# Proton_Schematic_Eagle.net
KiCad netlist of a schematic drawn in EAGLE
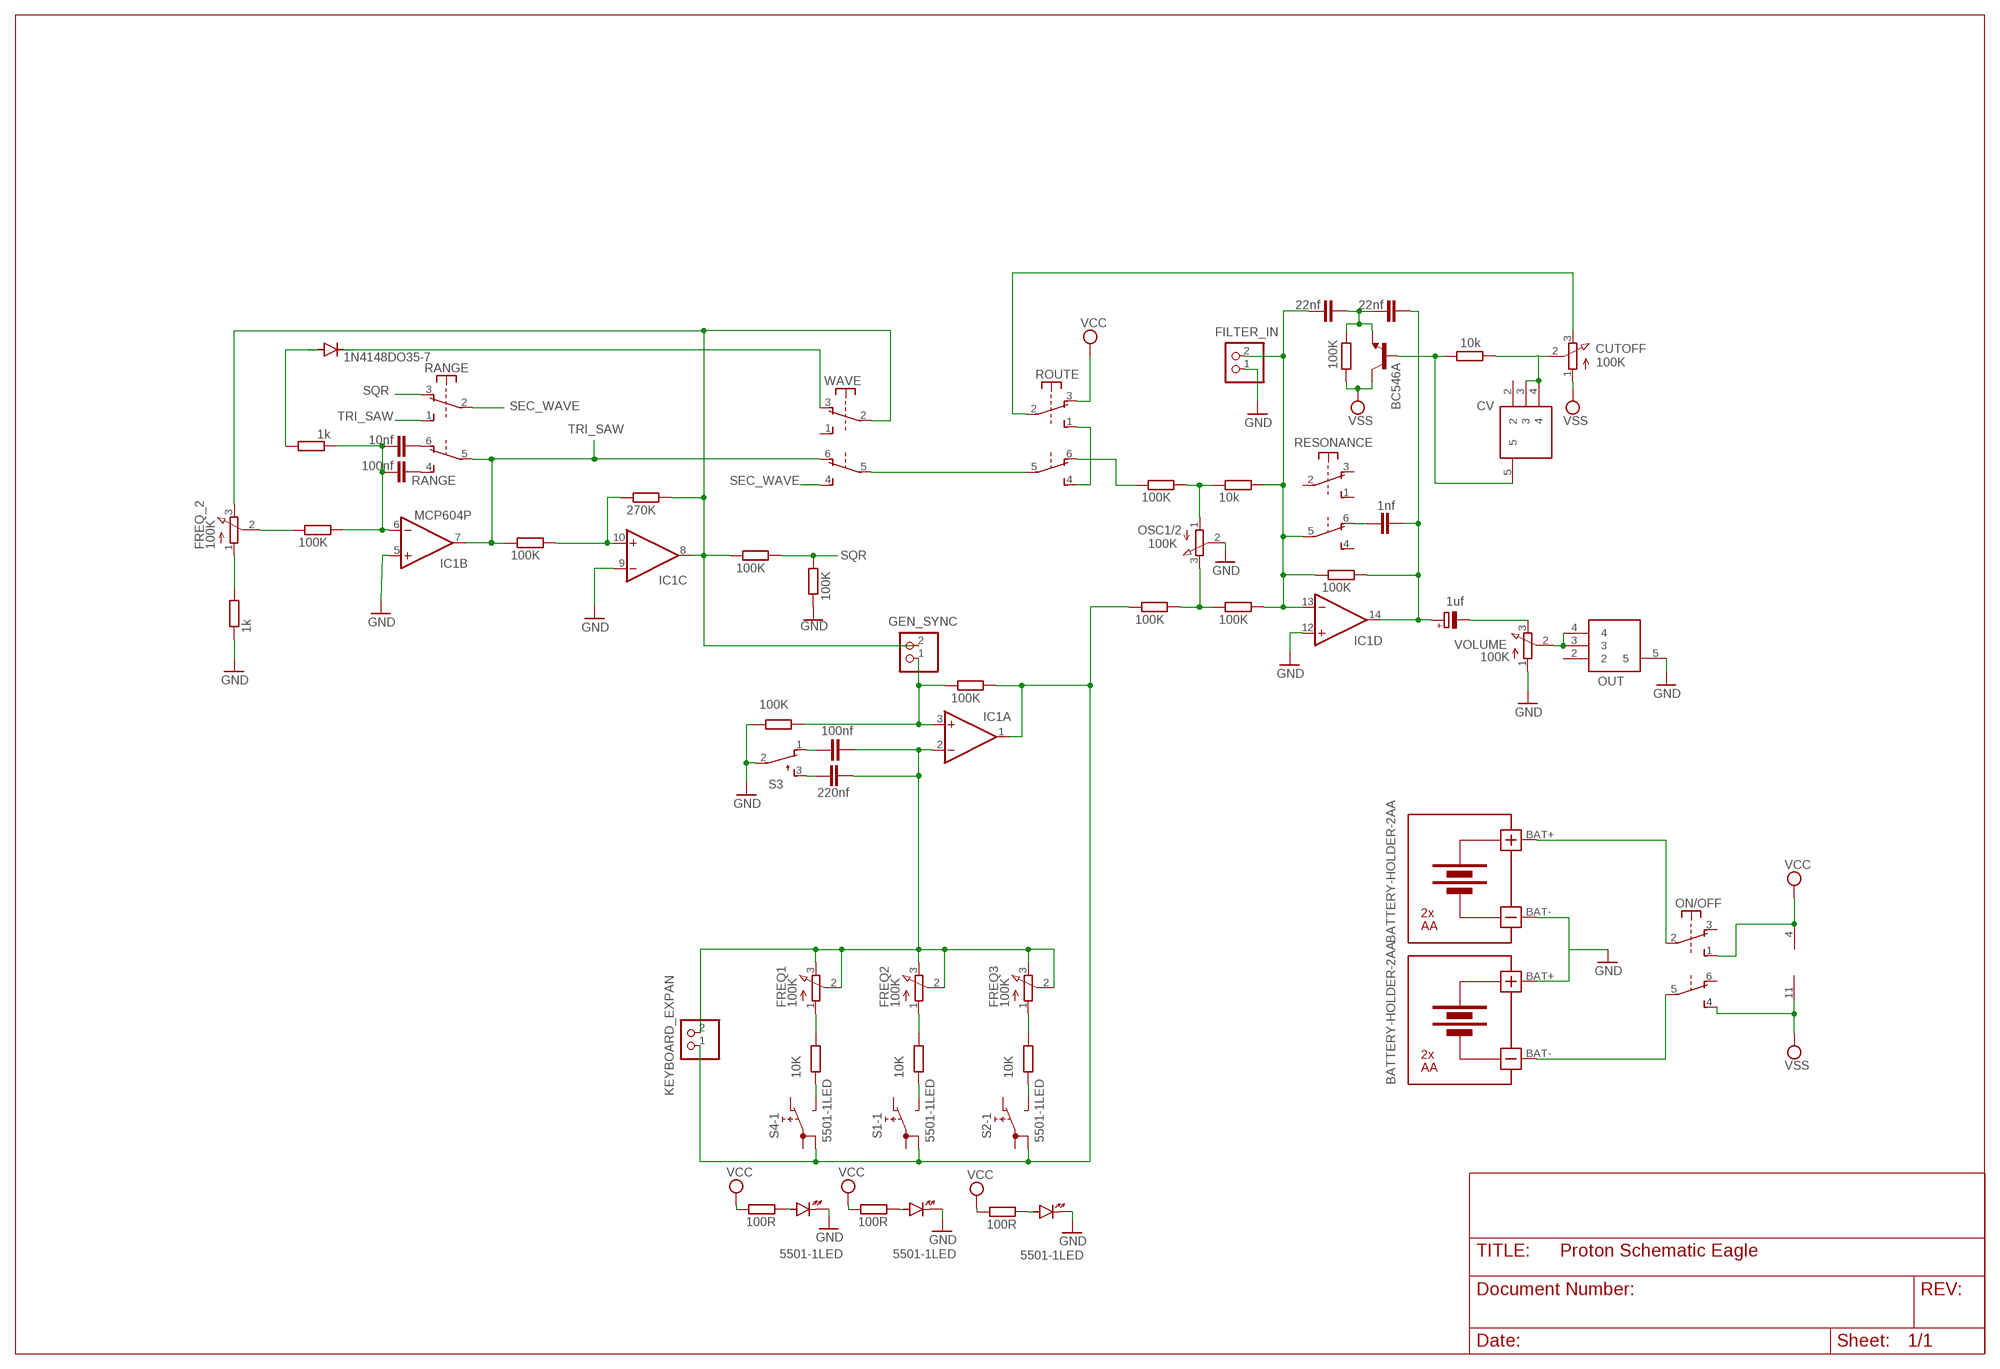
[diagram p0: schematic, sheet 1]

(export (version "E")
  (design (tool "Eeschema 10.0.6"))
  (components
    (comp (ref "1K")
      (value "1k")
      (footprint "eagle-import:0207_10")
      (libsource (lib "eagle-import") (part "R-EU_0207/10"))
    )
    (comp (ref "1K1")
      (value "1k")
      (footprint "eagle-import:0207_10")
      (libsource (lib "eagle-import") (part "R-EU_0207/10"))
    )
    (comp (ref "100K")
      (value "100K")
      (footprint "eagle-import:0207_10")
      (libsource (lib "eagle-import") (part "R-EU_0207/10"))
    )
    (comp (ref "100K1")
      (value "100K")
      (footprint "eagle-import:0207_10")
      (libsource (lib "eagle-import") (part "R-EU_0207/10"))
    )
    (comp (ref "100K2")
      (value "270K")
      (footprint "eagle-import:0207_10")
      (libsource (lib "eagle-import") (part "R-EU_0207/10"))
    )
    (comp (ref "100K3")
      (value "100K")
      (footprint "eagle-import:0207_10")
      (libsource (lib "eagle-import") (part "R-EU_0207/10"))
    )
    (comp (ref "100K4")
      (value "100K")
      (footprint "eagle-import:0207_10")
      (libsource (lib "eagle-import") (part "R-EU_0207/10"))
    )
    (comp (ref "100K5")
      (value "100K")
      (footprint "eagle-import:0207_10")
      (libsource (lib "eagle-import") (part "R-EU_0207/10"))
    )
    (comp (ref "100K6")
      (value "10k")
      (footprint "eagle-import:0207_10")
      (libsource (lib "eagle-import") (part "R-EU_0207/10"))
    )
    (comp (ref "100K7")
      (value "100K")
      (footprint "eagle-import:0207_10")
      (libsource (lib "eagle-import") (part "R-EU_0207/10"))
    )
    (comp (ref "100K8")
      (value "100K")
      (footprint "eagle-import:0207_10")
      (libsource (lib "eagle-import") (part "R-EU_0207/10"))
    )
    (comp (ref "100K9")
      (value "100K")
      (footprint "eagle-import:0207_10")
      (libsource (lib "eagle-import") (part "R-EU_0207/10"))
    )
    (comp (ref "100K10")
      (value "10k")
      (footprint "eagle-import:0207_10")
      (libsource (lib "eagle-import") (part "R-EU_0207/10"))
    )
    (comp (ref "100K11")
      (value "100K")
      (footprint "eagle-import:0207_10")
      (libsource (lib "eagle-import") (part "R-EU_0207/10"))
    )
    (comp (ref "100K12")
      (value "100K")
      (footprint "eagle-import:0207_10")
      (libsource (lib "eagle-import") (part "R-EU_0207/10"))
    )
    (comp (ref "100K13")
      (value "100K")
      (footprint "eagle-import:0207_10")
      (libsource (lib "eagle-import") (part "R-EU_0207/10"))
    )
    (comp (ref "100K14")
      (value "10K")
      (footprint "eagle-import:0207_10")
      (libsource (lib "eagle-import") (part "R-EU_0207/10"))
    )
    (comp (ref "100K15")
      (value "10K")
      (footprint "eagle-import:0207_10")
      (libsource (lib "eagle-import") (part "R-EU_0207/10"))
    )
    (comp (ref "100K16")
      (value "10K")
      (footprint "eagle-import:0207_10")
      (libsource (lib "eagle-import") (part "R-EU_0207/10"))
    )
    (comp (ref "100K18")
      (value "100R")
      (footprint "eagle-import:0207_10")
      (libsource (lib "eagle-import") (part "R-EU_0207/10"))
    )
    (comp (ref "100K19")
      (value "100R")
      (footprint "eagle-import:0207_10")
      (libsource (lib "eagle-import") (part "R-EU_0207/10"))
    )
    (comp (ref "100K20")
      (value "100R")
      (footprint "eagle-import:0207_10")
      (libsource (lib "eagle-import") (part "R-EU_0207/10"))
    )
    (comp (ref "C1")
      (value "100nf")
      (footprint "eagle-import:C050-024X044")
      (libsource (lib "eagle-import") (part "C-EU050-024X044"))
    )
    (comp (ref "C2")
      (value "10nf")
      (footprint "eagle-import:C050-024X044")
      (libsource (lib "eagle-import") (part "C-EU050-024X044"))
    )
    (comp (ref "C3")
      (value "22nf")
      (footprint "eagle-import:C050-024X044")
      (libsource (lib "eagle-import") (part "C-EU050-024X044"))
    )
    (comp (ref "C4")
      (value "22nf")
      (footprint "eagle-import:C050-024X044")
      (libsource (lib "eagle-import") (part "C-EU050-024X044"))
    )
    (comp (ref "C5")
      (value "1nf")
      (footprint "eagle-import:C050-024X044")
      (libsource (lib "eagle-import") (part "C-EU050-024X044"))
    )
    (comp (ref "C6")
      (value "220nf")
      (footprint "eagle-import:C050-024X044")
      (libsource (lib "eagle-import") (part "C-EU050-024X044"))
    )
    (comp (ref "C7")
      (value "100nf")
      (footprint "eagle-import:C050-024X044")
      (libsource (lib "eagle-import") (part "C-EU050-024X044"))
    )
    (comp (ref "C8")
      (value "1uf")
      (footprint "eagle-import:E2,5-5")
      (libsource (lib "eagle-import") (part "CPOL-EUE2.5-5"))
    )
    (comp (ref "CUTOFF")
      (value "100K")
      (footprint "eagle-import:EVUFXM")
      (libsource (lib "eagle-import") (part "EVUMF2"))
    )
    (comp (ref "CV")
      (value "PJ-320A")
      (footprint "eagle-import:PJ320A")
      (libsource (lib "eagle-import") (part "PJ-320A"))
    )
    (comp (ref "D1")
      (value "1N4148DO35-7")
      (footprint "eagle-import:DO35-7")
      (libsource (lib "eagle-import") (part "1N4148DO35-7"))
    )
    (comp (ref "FILTER_IN")
      (value "PINHD-1X2")
      (footprint "eagle-import:1X02")
      (libsource (lib "eagle-import") (part "PINHD-1X2"))
    )
    (comp (ref "FREQ1")
      (value "100K")
      (footprint "eagle-import:EVUFXM")
      (libsource (lib "eagle-import") (part "EVUMF2"))
    )
    (comp (ref "FREQ2")
      (value "100K")
      (footprint "eagle-import:EVUFXM")
      (libsource (lib "eagle-import") (part "EVUMF2"))
    )
    (comp (ref "FREQ3")
      (value "100K")
      (footprint "eagle-import:EVUFXM")
      (libsource (lib "eagle-import") (part "EVUMF2"))
    )
    (comp (ref "FREQ_2")
      (value "100K")
      (footprint "eagle-import:EVUFXM")
      (libsource (lib "eagle-import") (part "EVUMF2"))
    )
    (comp (ref "GEN_SYNC")
      (value "PINHD-1X2")
      (footprint "eagle-import:1X02")
      (libsource (lib "eagle-import") (part "PINHD-1X2"))
    )
    (comp (ref "IC1")
      (value "MCP604P")
      (footprint "eagle-import:DIL14")
      (libsource (lib "eagle-import") (part "MCP604P"))
    )
    (comp (ref "KEYBOARD_EXPAN")
      (value "PINHD-1X2")
      (footprint "eagle-import:1X02")
      (libsource (lib "eagle-import") (part "PINHD-1X2"))
    )
    (comp (ref "ON/OFF")
      (value "SWITCH-6PIN")
      (footprint "eagle-import:SWITCH-6PIN")
      (libsource (lib "eagle-import") (part "SWITCH-6PIN"))
    )
    (comp (ref "OSC1/2")
      (value "100K")
      (footprint "eagle-import:EVUFXM")
      (libsource (lib "eagle-import") (part "EVUMF2"))
    )
    (comp (ref "OUT")
      (value "PJ-320A")
      (footprint "eagle-import:PJ320A")
      (libsource (lib "eagle-import") (part "PJ-320A"))
    )
    (comp (ref "Q1")
      (value "BC546A")
      (footprint "eagle-import:TO92-EBC")
      (libsource (lib "eagle-import") (part "BC546A"))
    )
    (comp (ref "RANGE")
      (value "SWITCH-6PIN")
      (footprint "eagle-import:SWITCH-6PIN")
      (libsource (lib "eagle-import") (part "SWITCH-6PIN"))
    )
    (comp (ref "RESONANCE")
      (value "SWITCH-6PIN")
      (footprint "eagle-import:SWITCH-6PIN")
      (libsource (lib "eagle-import") (part "SWITCH-6PIN"))
    )
    (comp (ref "ROUTE")
      (value "SWITCH-6PIN")
      (footprint "eagle-import:SWITCH-6PIN")
      (libsource (lib "eagle-import") (part "SWITCH-6PIN"))
    )
    (comp (ref "S1")
      (value "5501-1LED")
      (footprint "eagle-import:5501-1LED")
      (libsource (lib "eagle-import") (part "55?-1LED01"))
    )
    (comp (ref "S2")
      (value "5501-1LED")
      (footprint "eagle-import:5501-1LED")
      (libsource (lib "eagle-import") (part "55?-1LED01"))
    )
    (comp (ref "S3")
      (value "TL32YO")
      (footprint "eagle-import:TL3XYO")
      (libsource (lib "eagle-import") (part "TL32YO"))
    )
    (comp (ref "S4")
      (value "5501-1LED")
      (footprint "eagle-import:5501-1LED")
      (libsource (lib "eagle-import") (part "55?-1LED01"))
    )
    (comp (ref "U$1")
      (value "BATTERY-HOLDER-2AA")
      (footprint "eagle-import:BATTERY-HOLDER-2AA")
      (libsource (lib "eagle-import") (part "BATTERY-HOLDER-2AA"))
    )
    (comp (ref "U$2")
      (value "BATTERY-HOLDER-2AA")
      (footprint "eagle-import:BATTERY-HOLDER-2AA")
      (libsource (lib "eagle-import") (part "BATTERY-HOLDER-2AA"))
    )
    (comp (ref "VOLUME")
      (value "100K")
      (footprint "eagle-import:EVUFXM")
      (libsource (lib "eagle-import") (part "EVUMF2"))
    )
    (comp (ref "WAVE")
      (value "SWITCH-6PIN")
      (footprint "eagle-import:SWITCH-6PIN")
      (libsource (lib "eagle-import") (part "SWITCH-6PIN"))
    )
  )
  (nets
    (net (code "1") (name "/SEC_WAVE") (class "Default")
      (node (ref "RANGE") (pin "2") (pinfunction "P_2") (pintype "passive"))
      (node (ref "WAVE") (pin "4") (pinfunction "S_4") (pintype "passive"))
    )
    (net (code "2") (name "/SQR") (class "Default")
      (node (ref "100K3") (pin "2") (pinfunction "2_2") (pintype "passive"))
      (node (ref "100K4") (pin "2") (pinfunction "2_2") (pintype "passive"))
      (node (ref "RANGE") (pin "3") (pinfunction "O_3") (pintype "passive"))
    )
    (net (code "3") (name "/TRI_SAW") (class "Default")
      (node (ref "100K1") (pin "1") (pinfunction "1_1") (pintype "passive"))
      (node (ref "IC1") (pin "7") (pinfunction "OUT_7") (pintype "output"))
      (node (ref "RANGE") (pin "1") (pinfunction "S_1") (pintype "passive"))
      (node (ref "RANGE") (pin "5") (pinfunction "P_5") (pintype "passive"))
      (node (ref "WAVE") (pin "6") (pinfunction "O_6") (pintype "passive"))
    )
    (net (code "4") (name "GND") (class "Default")
      (node (ref "100K13") (pin "1") (pinfunction "1_1") (pintype "passive"))
      (node (ref "100K4") (pin "1") (pinfunction "1_1") (pintype "passive"))
      (node (ref "1K") (pin "1") (pinfunction "1_1") (pintype "passive"))
      (node (ref "FILTER_IN") (pin "1") (pinfunction "1_1") (pintype "passive"))
      (node (ref "IC1") (pin "12") (pinfunction "+IN_12") (pintype "input"))
      (node (ref "IC1") (pin "5") (pinfunction "+IN_5") (pintype "input"))
      (node (ref "IC1") (pin "9") (pinfunction "-IN_9") (pintype "input"))
      (node (ref "OSC1/2") (pin "2") (pinfunction "S_2") (pintype "passive"))
      (node (ref "OUT") (pin "5") (pinfunction "5_5") (pintype "bidirectional"))
      (node (ref "S1") (pin "-") (pinfunction "K_-") (pintype "passive"))
      (node (ref "S2") (pin "-") (pinfunction "K_-") (pintype "passive"))
      (node (ref "S3") (pin "2") (pinfunction "P_2") (pintype "passive"))
      (node (ref "S4") (pin "-") (pinfunction "K_-") (pintype "passive"))
      (node (ref "U$1") (pin "BAT-") (pinfunction "BAT-_BAT-") (pintype "power_in"))
      (node (ref "U$2") (pin "BAT+") (pinfunction "BAT+_BAT+") (pintype "power_in"))
      (node (ref "VOLUME") (pin "1") (pinfunction "A_1") (pintype "passive"))
    )
    (net (code "5") (name "Net-(1K1-Pad2)") (class "Default")
      (node (ref "1K1") (pin "2") (pinfunction "2_2") (pintype "passive"))
      (node (ref "D1") (pin "A") (pinfunction "A_A") (pintype "passive"))
    )
    (net (code "6") (name "Net-(100K9-Pad2)") (class "Default")
      (node (ref "100K9") (pin "2") (pinfunction "2_2") (pintype "passive"))
      (node (ref "C3") (pin "2") (pinfunction "2_2") (pintype "passive"))
      (node (ref "C4") (pin "1") (pinfunction "1_1") (pintype "passive"))
      (node (ref "Q1") (pin "E") (pinfunction "E_E") (pintype "passive"))
    )
    (net (code "7") (name "Net-(100K10-Pad1)") (class "Default")
      (node (ref "100K10") (pin "1") (pinfunction "1_1") (pintype "passive"))
      (node (ref "CV") (pin "5") (pinfunction "5_5") (pintype "bidirectional"))
      (node (ref "Q1") (pin "B") (pinfunction "B_B") (pintype "passive"))
    )
    (net (code "8") (name "Net-(100K14-Pad1)") (class "Default")
      (node (ref "100K14") (pin "1") (pinfunction "1_1") (pintype "passive"))
      (node (ref "S4") (pin "NO") (pinfunction "NO_NO") (pintype "passive"))
    )
    (net (code "9") (name "Net-(100K15-Pad1)") (class "Default")
      (node (ref "100K15") (pin "1") (pinfunction "1_1") (pintype "passive"))
      (node (ref "S1") (pin "NO") (pinfunction "NO_NO") (pintype "passive"))
    )
    (net (code "10") (name "Net-(100K16-Pad1)") (class "Default")
      (node (ref "100K16") (pin "1") (pinfunction "1_1") (pintype "passive"))
      (node (ref "S2") (pin "NO") (pinfunction "NO_NO") (pintype "passive"))
    )
    (net (code "11") (name "Net-(CUTOFF-E)") (class "Default")
      (node (ref "CUTOFF") (pin "3") (pinfunction "E_3") (pintype "passive"))
      (node (ref "ROUTE") (pin "2") (pinfunction "P_2") (pintype "passive"))
    )
    (net (code "12") (name "Net-(CUTOFF-S)") (class "Default")
      (node (ref "100K10") (pin "2") (pinfunction "2_2") (pintype "passive"))
      (node (ref "CUTOFF") (pin "2") (pinfunction "S_2") (pintype "passive"))
      (node (ref "CV") (pin "3") (pinfunction "3_3") (pintype "bidirectional"))
      (node (ref "CV") (pin "4") (pinfunction "4_4") (pintype "bidirectional"))
    )
    (net (code "13") (name "Net-(FREQ1-A)") (class "Default")
      (node (ref "100K14") (pin "2") (pinfunction "2_2") (pintype "passive"))
      (node (ref "FREQ1") (pin "1") (pinfunction "A_1") (pintype "passive"))
    )
    (net (code "14") (name "Net-(FREQ1-E)") (class "Default")
      (node (ref "C6") (pin "2") (pinfunction "2_2") (pintype "passive"))
      (node (ref "C7") (pin "2") (pinfunction "2_2") (pintype "passive"))
      (node (ref "FREQ1") (pin "2") (pinfunction "S_2") (pintype "passive"))
      (node (ref "FREQ1") (pin "3") (pinfunction "E_3") (pintype "passive"))
      (node (ref "FREQ2") (pin "2") (pinfunction "S_2") (pintype "passive"))
      (node (ref "FREQ2") (pin "3") (pinfunction "E_3") (pintype "passive"))
      (node (ref "FREQ3") (pin "2") (pinfunction "S_2") (pintype "passive"))
      (node (ref "FREQ3") (pin "3") (pinfunction "E_3") (pintype "passive"))
      (node (ref "IC1") (pin "2") (pinfunction "-IN_2") (pintype "input"))
      (node (ref "KEYBOARD_EXPAN") (pin "2") (pinfunction "2_2") (pintype "passive"))
    )
    (net (code "15") (name "Net-(FREQ2-A)") (class "Default")
      (node (ref "100K15") (pin "2") (pinfunction "2_2") (pintype "passive"))
      (node (ref "FREQ2") (pin "1") (pinfunction "A_1") (pintype "passive"))
    )
    (net (code "16") (name "Net-(FREQ3-A)") (class "Default")
      (node (ref "100K16") (pin "2") (pinfunction "2_2") (pintype "passive"))
      (node (ref "FREQ3") (pin "1") (pinfunction "A_1") (pintype "passive"))
    )
    (net (code "17") (name "Net-(FREQ_2-A)") (class "Default")
      (node (ref "1K") (pin "2") (pinfunction "2_2") (pintype "passive"))
      (node (ref "FREQ_2") (pin "1") (pinfunction "A_1") (pintype "passive"))
    )
    (net (code "18") (name "Net-(FREQ_2-E)") (class "Default")
      (node (ref "100K2") (pin "2") (pinfunction "2_2") (pintype "passive"))
      (node (ref "100K3") (pin "1") (pinfunction "1_1") (pintype "passive"))
      (node (ref "FREQ_2") (pin "3") (pinfunction "E_3") (pintype "passive"))
      (node (ref "GEN_SYNC") (pin "2") (pinfunction "2_2") (pintype "passive"))
      (node (ref "IC1") (pin "8") (pinfunction "OUT_8") (pintype "output"))
      (node (ref "WAVE") (pin "2") (pinfunction "P_2") (pintype "passive"))
    )
    (net (code "19") (name "Net-(FREQ_2-S)") (class "Default")
      (node (ref "100K") (pin "1") (pinfunction "1_1") (pintype "passive"))
      (node (ref "FREQ_2") (pin "2") (pinfunction "S_2") (pintype "passive"))
    )
    (net (code "20") (name "Net-(IC1A-+IN)") (class "Default")
      (node (ref "100K12") (pin "1") (pinfunction "1_1") (pintype "passive"))
      (node (ref "100K13") (pin "2") (pinfunction "2_2") (pintype "passive"))
      (node (ref "GEN_SYNC") (pin "1") (pinfunction "1_1") (pintype "passive"))
      (node (ref "IC1") (pin "3") (pinfunction "+IN_3") (pintype "input"))
    )
    (net (code "21") (name "Net-(IC1A-OUT)") (class "Default")
      (node (ref "100K12") (pin "2") (pinfunction "2_2") (pintype "passive"))
      (node (ref "100K7") (pin "1") (pinfunction "1_1") (pintype "passive"))
      (node (ref "IC1") (pin "1") (pinfunction "OUT_1") (pintype "output"))
      (node (ref "KEYBOARD_EXPAN") (pin "1") (pinfunction "1_1") (pintype "passive"))
      (node (ref "S1") (pin "1B") (pinfunction "1B_1B") (pintype "passive"))
      (node (ref "S2") (pin "1B") (pinfunction "1B_1B") (pintype "passive"))
      (node (ref "S4") (pin "1B") (pinfunction "1B_1B") (pintype "passive"))
    )
    (net (code "22") (name "Net-(IC1B--IN)") (class "Default")
      (node (ref "100K") (pin "2") (pinfunction "2_2") (pintype "passive"))
      (node (ref "1K1") (pin "1") (pinfunction "1_1") (pintype "passive"))
      (node (ref "C1") (pin "1") (pinfunction "1_1") (pintype "passive"))
      (node (ref "C2") (pin "1") (pinfunction "1_1") (pintype "passive"))
      (node (ref "IC1") (pin "6") (pinfunction "-IN_6") (pintype "input"))
    )
    (net (code "23") (name "Net-(IC1C-+IN)") (class "Default")
      (node (ref "100K1") (pin "2") (pinfunction "2_2") (pintype "passive"))
      (node (ref "100K2") (pin "1") (pinfunction "1_1") (pintype "passive"))
      (node (ref "IC1") (pin "10") (pinfunction "+IN_10") (pintype "input"))
    )
    (net (code "24") (name "Net-(IC1D--IN)") (class "Default")
      (node (ref "100K11") (pin "1") (pinfunction "1_1") (pintype "passive"))
      (node (ref "100K6") (pin "2") (pinfunction "2_2") (pintype "passive"))
      (node (ref "100K8") (pin "2") (pinfunction "2_2") (pintype "passive"))
      (node (ref "C3") (pin "1") (pinfunction "1_1") (pintype "passive"))
      (node (ref "FILTER_IN") (pin "2") (pinfunction "2_2") (pintype "passive"))
      (node (ref "IC1") (pin "13") (pinfunction "-IN_13") (pintype "input"))
      (node (ref "RESONANCE") (pin "5") (pinfunction "P_5") (pintype "passive"))
    )
    (net (code "25") (name "Net-(IC1D-OUT)") (class "Default")
      (node (ref "100K11") (pin "2") (pinfunction "2_2") (pintype "passive"))
      (node (ref "C4") (pin "2") (pinfunction "2_2") (pintype "passive"))
      (node (ref "C5") (pin "2") (pinfunction "2_2") (pintype "passive"))
      (node (ref "C8") (pin "+") (pinfunction "+_+") (pintype "passive"))
      (node (ref "IC1") (pin "14") (pinfunction "OUT_14") (pintype "output"))
    )
    (net (code "26") (name "Net-(ON/OFFA-P)") (class "Default")
      (node (ref "ON/OFF") (pin "2") (pinfunction "P_2") (pintype "passive"))
      (node (ref "U$1") (pin "BAT+") (pinfunction "BAT+_BAT+") (pintype "power_in"))
    )
    (net (code "27") (name "Net-(ON/OFFB-P)") (class "Default")
      (node (ref "ON/OFF") (pin "5") (pinfunction "P_5") (pintype "passive"))
      (node (ref "U$2") (pin "BAT-") (pinfunction "BAT-_BAT-") (pintype "power_in"))
    )
    (net (code "28") (name "Net-(OSC1/2-A)") (class "Default")
      (node (ref "100K5") (pin "2") (pinfunction "2_2") (pintype "passive"))
      (node (ref "100K6") (pin "1") (pinfunction "1_1") (pintype "passive"))
      (node (ref "OSC1/2") (pin "1") (pinfunction "A_1") (pintype "passive"))
    )
    (net (code "29") (name "Net-(OSC1/2-E)") (class "Default")
      (node (ref "100K7") (pin "2") (pinfunction "2_2") (pintype "passive"))
      (node (ref "100K8") (pin "1") (pinfunction "1_1") (pintype "passive"))
      (node (ref "OSC1/2") (pin "3") (pinfunction "E_3") (pintype "passive"))
    )
    (net (code "30") (name "Net-(RANGEB-O)") (class "Default")
      (node (ref "C2") (pin "2") (pinfunction "2_2") (pintype "passive"))
      (node (ref "RANGE") (pin "6") (pinfunction "O_6") (pintype "passive"))
    )
    (net (code "31") (name "Net-(RANGEB-S)") (class "Default")
      (node (ref "C1") (pin "2") (pinfunction "2_2") (pintype "passive"))
      (node (ref "RANGE") (pin "4") (pinfunction "S_4") (pintype "passive"))
    )
    (net (code "32") (name "Net-(RESONANCEB-O)") (class "Default")
      (node (ref "C5") (pin "1") (pinfunction "1_1") (pintype "passive"))
      (node (ref "RESONANCE") (pin "6") (pinfunction "O_6") (pintype "passive"))
    )
    (net (code "33") (name "Net-(ROUTEA-S)") (class "Default")
      (node (ref "ROUTE") (pin "1") (pinfunction "S_1") (pintype "passive"))
      (node (ref "ROUTE") (pin "4") (pinfunction "S_4") (pintype "passive"))
    )
    (net (code "34") (name "Net-(ROUTEB-O)") (class "Default")
      (node (ref "100K5") (pin "1") (pinfunction "1_1") (pintype "passive"))
      (node (ref "ROUTE") (pin "6") (pinfunction "O_6") (pintype "passive"))
    )
    (net (code "35") (name "Net-(ROUTEB-P)") (class "Default")
      (node (ref "ROUTE") (pin "5") (pinfunction "P_5") (pintype "passive"))
      (node (ref "WAVE") (pin "5") (pinfunction "P_5") (pintype "passive"))
    )
    (net (code "36") (name "Net-(S1B-A)") (class "Default")
      (node (ref "100K19") (pin "1") (pinfunction "1_1") (pintype "passive"))
      (node (ref "S1") (pin "+") (pinfunction "A_+") (pintype "passive"))
    )
    (net (code "37") (name "Net-(S2B-A)") (class "Default")
      (node (ref "100K20") (pin "1") (pinfunction "1_1") (pintype "passive"))
      (node (ref "S2") (pin "+") (pinfunction "A_+") (pintype "passive"))
    )
    (net (code "38") (name "Net-(S3-O)") (class "Default")
      (node (ref "C7") (pin "1") (pinfunction "1_1") (pintype "passive"))
      (node (ref "S3") (pin "1") (pinfunction "O_1") (pintype "passive"))
    )
    (net (code "39") (name "Net-(S3-S)") (class "Default")
      (node (ref "C6") (pin "1") (pinfunction "1_1") (pintype "passive"))
      (node (ref "S3") (pin "3") (pinfunction "S_3") (pintype "passive"))
    )
    (net (code "40") (name "Net-(S4B-A)") (class "Default")
      (node (ref "100K18") (pin "1") (pinfunction "1_1") (pintype "passive"))
      (node (ref "S4") (pin "+") (pinfunction "A_+") (pintype "passive"))
    )
    (net (code "41") (name "Net-(VOLUME-E)") (class "Default")
      (node (ref "C8") (pin "-") (pinfunction "-_-") (pintype "passive"))
      (node (ref "VOLUME") (pin "3") (pinfunction "E_3") (pintype "passive"))
    )
    (net (code "42") (name "Net-(VOLUME-S)") (class "Default")
      (node (ref "OUT") (pin "3") (pinfunction "3_3") (pintype "bidirectional"))
      (node (ref "OUT") (pin "4") (pinfunction "4_4") (pintype "bidirectional"))
      (node (ref "VOLUME") (pin "2") (pinfunction "S_2") (pintype "passive"))
    )
    (net (code "43") (name "Net-(WAVEA-O)") (class "Default")
      (node (ref "D1") (pin "C") (pinfunction "C_C") (pintype "passive"))
      (node (ref "WAVE") (pin "3") (pinfunction "O_3") (pintype "passive"))
    )
    (net (code "44") (name "VCC") (class "Default")
      (node (ref "100K18") (pin "2") (pinfunction "2_2") (pintype "passive"))
      (node (ref "100K19") (pin "2") (pinfunction "2_2") (pintype "passive"))
      (node (ref "100K20") (pin "2") (pinfunction "2_2") (pintype "passive"))
      (node (ref "IC1") (pin "4") (pinfunction "V+_4") (pintype "power_in"))
      (node (ref "ON/OFF") (pin "1") (pinfunction "S_1") (pintype "passive"))
      (node (ref "ROUTE") (pin "3") (pinfunction "O_3") (pintype "passive"))
    )
    (net (code "45") (name "VSS") (class "Default")
      (node (ref "100K9") (pin "1") (pinfunction "1_1") (pintype "passive"))
      (node (ref "CUTOFF") (pin "1") (pinfunction "A_1") (pintype "passive"))
      (node (ref "IC1") (pin "11") (pinfunction "V-_11") (pintype "power_in"))
      (node (ref "ON/OFF") (pin "4") (pinfunction "S_4") (pintype "passive"))
      (node (ref "Q1") (pin "C") (pinfunction "C_C") (pintype "passive"))
    )
    (net (code "46") (name "unconnected-(CV-Pad2)") (class "Default")
      (node (ref "CV") (pin "2") (pinfunction "2_2") (pintype "bidirectional"))
    )
    (net (code "47") (name "unconnected-(ON/OFFA-O-Pad3)") (class "Default")
      (node (ref "ON/OFF") (pin "3") (pinfunction "O_3") (pintype "passive"))
    )
    (net (code "48") (name "unconnected-(ON/OFFB-O-Pad6)") (class "Default")
      (node (ref "ON/OFF") (pin "6") (pinfunction "O_6") (pintype "passive"))
    )
    (net (code "49") (name "unconnected-(OUT-Pad2)") (class "Default")
      (node (ref "OUT") (pin "2") (pinfunction "2_2") (pintype "bidirectional"))
    )
    (net (code "50") (name "unconnected-(RESONANCEA-O-Pad3)") (class "Default")
      (node (ref "RESONANCE") (pin "3") (pinfunction "O_3") (pintype "passive"))
    )
    (net (code "51") (name "unconnected-(RESONANCEA-P-Pad2)") (class "Default")
      (node (ref "RESONANCE") (pin "2") (pinfunction "P_2") (pintype "passive"))
    )
    (net (code "52") (name "unconnected-(RESONANCEA-S-Pad1)") (class "Default")
      (node (ref "RESONANCE") (pin "1") (pinfunction "S_1") (pintype "passive"))
    )
    (net (code "53") (name "unconnected-(RESONANCEB-S-Pad4)") (class "Default")
      (node (ref "RESONANCE") (pin "4") (pinfunction "S_4") (pintype "passive"))
    )
    (net (code "54") (name "unconnected-(S1-Pad1A)") (class "Default")
      (node (ref "S1") (pin "1A") (pinfunction "1A_1A") (pintype "passive"))
    )
    (net (code "55") (name "unconnected-(S1-PadNC)") (class "Default")
      (node (ref "S1") (pin "NC") (pinfunction "NC_NC") (pintype "passive"))
    )
    (net (code "56") (name "unconnected-(S2-Pad1A)") (class "Default")
      (node (ref "S2") (pin "1A") (pinfunction "1A_1A") (pintype "passive"))
    )
    (net (code "57") (name "unconnected-(S2-PadNC)") (class "Default")
      (node (ref "S2") (pin "NC") (pinfunction "NC_NC") (pintype "passive"))
    )
    (net (code "58") (name "unconnected-(S4-Pad1A)") (class "Default")
      (node (ref "S4") (pin "1A") (pinfunction "1A_1A") (pintype "passive"))
    )
    (net (code "59") (name "unconnected-(S4-PadNC)") (class "Default")
      (node (ref "S4") (pin "NC") (pinfunction "NC_NC") (pintype "passive"))
    )
    (net (code "60") (name "unconnected-(WAVEA-S-Pad1)") (class "Default")
      (node (ref "WAVE") (pin "1") (pinfunction "S_1") (pintype "passive"))
    )
  )
)
